# OLED_Shield.net
KiCad netlist of a schematic drawn in EAGLE
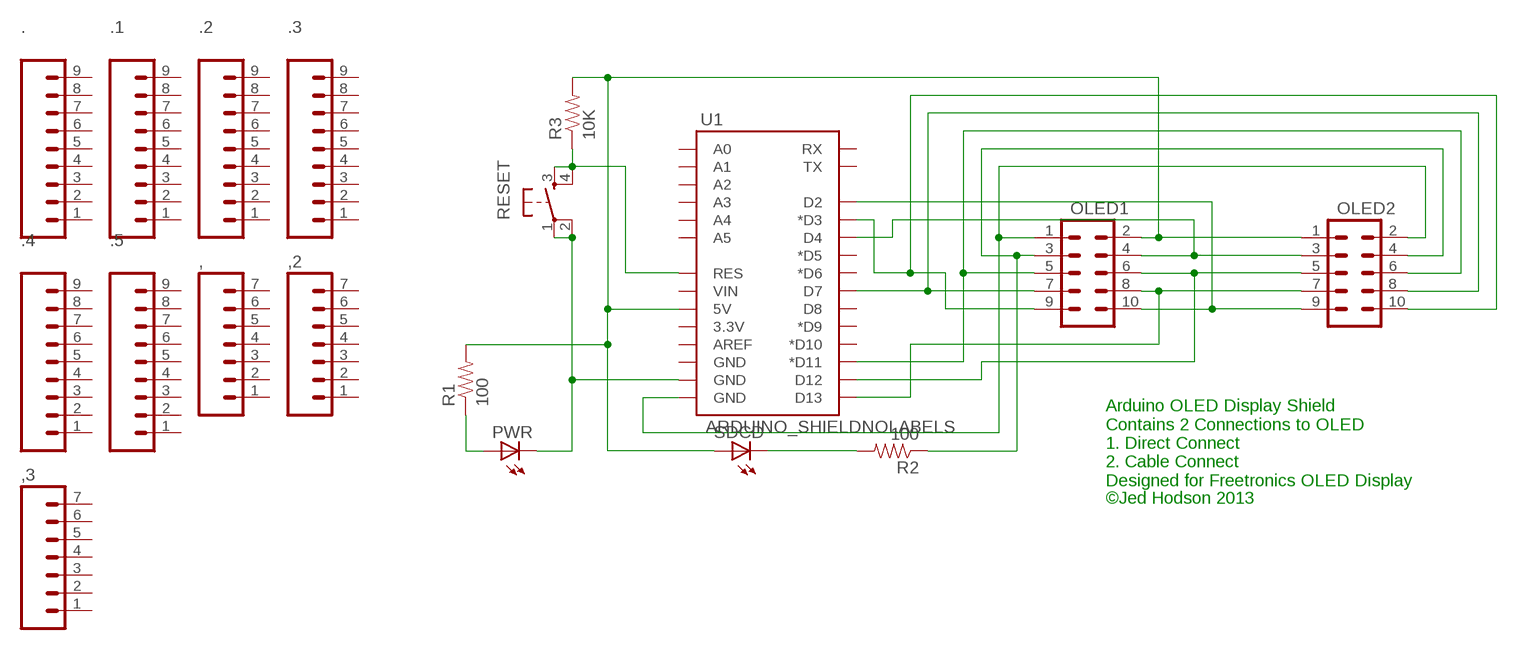
[diagram p0: schematic, sheet 1]

(export (version "E")
  (design (tool "Eeschema 10.0.6"))
  (components
    (comp (ref ",")
      (value "M07")
      (footprint "eagle-import:1X07")
      (libsource (lib "eagle-import") (part "M07"))
    )
    (comp (ref ",2")
      (value "M07")
      (footprint "eagle-import:1X07")
      (libsource (lib "eagle-import") (part "M07"))
    )
    (comp (ref ",3")
      (value "M07")
      (footprint "eagle-import:1X07")
      (libsource (lib "eagle-import") (part "M07"))
    )
    (comp (ref ".")
      (value "M09")
      (footprint "eagle-import:1X09")
      (libsource (lib "eagle-import") (part "M09"))
    )
    (comp (ref ".1")
      (value "M09")
      (footprint "eagle-import:1X09")
      (libsource (lib "eagle-import") (part "M09"))
    )
    (comp (ref ".2")
      (value "M09")
      (footprint "eagle-import:1X09")
      (libsource (lib "eagle-import") (part "M09"))
    )
    (comp (ref ".3")
      (value "M09")
      (footprint "eagle-import:1X09")
      (libsource (lib "eagle-import") (part "M09"))
    )
    (comp (ref ".4")
      (value "M09")
      (footprint "eagle-import:1X09")
      (libsource (lib "eagle-import") (part "M09"))
    )
    (comp (ref ".5")
      (value "M09")
      (footprint "eagle-import:1X09")
      (libsource (lib "eagle-import") (part "M09"))
    )
    (comp (ref "OLED1")
      (value "M05X2PTH")
      (footprint "eagle-import:AVR_ICSP")
      (libsource (lib "eagle-import") (part "M05X2PTH"))
    )
    (comp (ref "OLED2")
      (value "M05X2PTH")
      (footprint "eagle-import:AVR_ICSP")
      (libsource (lib "eagle-import") (part "M05X2PTH"))
    )
    (comp (ref "PWR")
      (value "LED5MM")
      (footprint "eagle-import:LED5MM")
      (libsource (lib "eagle-import") (part "LED5MM"))
    )
    (comp (ref "R1")
      (value "100")
      (footprint "eagle-import:AXIAL-0.4")
      (libsource (lib "eagle-import") (part "RESISTORPTH-1/4W"))
    )
    (comp (ref "R2")
      (value "100")
      (footprint "eagle-import:AXIAL-0.4")
      (libsource (lib "eagle-import") (part "RESISTORPTH-1/4W"))
    )
    (comp (ref "R3")
      (value "10K")
      (footprint "eagle-import:AXIAL-0.4")
      (libsource (lib "eagle-import") (part "RESISTORPTH-1/4W"))
    )
    (comp (ref "RESET")
      (value "TAC_SWITCHPTH")
      (footprint "eagle-import:TACTILE-PTH")
      (libsource (lib "eagle-import") (part "TAC_SWITCHPTH"))
    )
    (comp (ref "SDCD")
      (value "LED5MM")
      (footprint "eagle-import:LED5MM")
      (libsource (lib "eagle-import") (part "LED5MM"))
    )
    (comp (ref "U1")
      (value "ARDUINO_SHIELDNOLABELS")
      (footprint "eagle-import:DUEMILANOVE_SHIELD_NOLABELS")
      (libsource (lib "eagle-import") (part "ARDUINO_SHIELDNOLABELS"))
    )
  )
  (nets
    (net (code "1") (name "Net-(OLED1-Pad1)") (class "Default")
      (node (ref "OLED1") (pin "1") (pinfunction "1_1") (pintype "passive"))
      (node (ref "OLED2") (pin "2") (pinfunction "2_2") (pintype "passive"))
      (node (ref "U1") (pin "GND@0") (pinfunction "GND_GND@0") (pintype "bidirectional"))
    )
    (net (code "2") (name "Net-(OLED1-Pad4)") (class "Default")
      (node (ref "OLED1") (pin "4") (pinfunction "4_4") (pintype "passive"))
      (node (ref "OLED2") (pin "3") (pinfunction "3_3") (pintype "passive"))
      (node (ref "U1") (pin "D4") (pinfunction "D4_D4") (pintype "bidirectional"))
    )
    (net (code "3") (name "Net-(OLED1-Pad6)") (class "Default")
      (node (ref "OLED1") (pin "6") (pinfunction "6_6") (pintype "passive"))
      (node (ref "OLED2") (pin "5") (pinfunction "5_5") (pintype "passive"))
      (node (ref "U1") (pin "D12") (pinfunction "D12_D12") (pintype "bidirectional"))
    )
    (net (code "4") (name "Net-(OLED1-Pad7)") (class "Default")
      (node (ref "OLED1") (pin "7") (pinfunction "7_7") (pintype "passive"))
      (node (ref "OLED2") (pin "8") (pinfunction "8_8") (pintype "passive"))
      (node (ref "U1") (pin "D7") (pinfunction "D7_D7") (pintype "bidirectional"))
    )
    (net (code "5") (name "Net-(OLED1-Pad8)") (class "Default")
      (node (ref "OLED1") (pin "8") (pinfunction "8_8") (pintype "passive"))
      (node (ref "OLED2") (pin "7") (pinfunction "7_7") (pintype "passive"))
      (node (ref "U1") (pin "D13") (pinfunction "D13_D13") (pintype "bidirectional"))
    )
    (net (code "6") (name "Net-(OLED1-Pad10)") (class "Default")
      (node (ref "OLED1") (pin "10") (pinfunction "10_10") (pintype "passive"))
      (node (ref "OLED2") (pin "9") (pinfunction "9_9") (pintype "passive"))
      (node (ref "U1") (pin "D2") (pinfunction "D2_D2") (pintype "bidirectional"))
    )
    (net (code "7") (name "Net-(PWR-C)") (class "Default")
      (node (ref "PWR") (pin "K") (pinfunction "C_K") (pintype "passive"))
      (node (ref "RESET") (pin "1") (pinfunction "1_1") (pintype "passive"))
      (node (ref "RESET") (pin "2") (pinfunction "2_2") (pintype "passive"))
      (node (ref "U1") (pin "GND@1") (pinfunction "GND_GND@1") (pintype "bidirectional"))
    )
    (net (code "8") (name "Net-(R1-1)") (class "Default")
      (node (ref "PWR") (pin "A") (pinfunction "A_A") (pintype "passive"))
      (node (ref "R1") (pin "P$1") (pinfunction "1_P$1") (pintype "passive"))
    )
    (net (code "9") (name "Net-(R1-2)") (class "Default")
      (node (ref "OLED1") (pin "2") (pinfunction "2_2") (pintype "passive"))
      (node (ref "OLED2") (pin "1") (pinfunction "1_1") (pintype "passive"))
      (node (ref "R1") (pin "P$2") (pinfunction "2_P$2") (pintype "passive"))
      (node (ref "R3") (pin "P$2") (pinfunction "2_P$2") (pintype "passive"))
      (node (ref "SDCD") (pin "A") (pinfunction "A_A") (pintype "passive"))
      (node (ref "U1") (pin "5V") (pinfunction "5V_5V") (pintype "bidirectional"))
    )
    (net (code "10") (name "Net-(R2-1)") (class "Default")
      (node (ref "OLED1") (pin "3") (pinfunction "3_3") (pintype "passive"))
      (node (ref "OLED2") (pin "4") (pinfunction "4_4") (pintype "passive"))
      (node (ref "R2") (pin "P$1") (pinfunction "1_P$1") (pintype "passive"))
    )
    (net (code "11") (name "Net-(R2-2)") (class "Default")
      (node (ref "R2") (pin "P$2") (pinfunction "2_P$2") (pintype "passive"))
      (node (ref "SDCD") (pin "K") (pinfunction "C_K") (pintype "passive"))
    )
    (net (code "12") (name "Net-(R3-1)") (class "Default")
      (node (ref "R3") (pin "P$1") (pinfunction "1_P$1") (pintype "passive"))
      (node (ref "RESET") (pin "3") (pinfunction "3_3") (pintype "passive"))
      (node (ref "RESET") (pin "4") (pinfunction "4_4") (pintype "passive"))
      (node (ref "U1") (pin "RES") (pinfunction "RES_RES") (pintype "bidirectional"))
    )
    (net (code "13") (name "Net-(U1-*D3)") (class "Default")
      (node (ref "OLED1") (pin "9") (pinfunction "9_9") (pintype "passive"))
      (node (ref "OLED2") (pin "10") (pinfunction "10_10") (pintype "passive"))
      (node (ref "U1") (pin "D3") (pinfunction "*D3_D3") (pintype "bidirectional"))
    )
    (net (code "14") (name "Net-(U1-*D11)") (class "Default")
      (node (ref "OLED1") (pin "5") (pinfunction "5_5") (pintype "passive"))
      (node (ref "OLED2") (pin "6") (pinfunction "6_6") (pintype "passive"))
      (node (ref "U1") (pin "D11") (pinfunction "*D11_D11") (pintype "bidirectional"))
    )
    (net (code "15") (name "unconnected-(,-Pad1)") (class "Default")
      (node (ref ",") (pin "1") (pinfunction "1_1") (pintype "passive"))
    )
    (net (code "16") (name "unconnected-(,-Pad2)") (class "Default")
      (node (ref ",") (pin "2") (pinfunction "2_2") (pintype "passive"))
    )
    (net (code "17") (name "unconnected-(,-Pad3)") (class "Default")
      (node (ref ",") (pin "3") (pinfunction "3_3") (pintype "passive"))
    )
    (net (code "18") (name "unconnected-(,-Pad4)") (class "Default")
      (node (ref ",") (pin "4") (pinfunction "4_4") (pintype "passive"))
    )
    (net (code "19") (name "unconnected-(,-Pad5)") (class "Default")
      (node (ref ",") (pin "5") (pinfunction "5_5") (pintype "passive"))
    )
    (net (code "20") (name "unconnected-(,-Pad6)") (class "Default")
      (node (ref ",") (pin "6") (pinfunction "6_6") (pintype "passive"))
    )
    (net (code "21") (name "unconnected-(,-Pad7)") (class "Default")
      (node (ref ",") (pin "7") (pinfunction "7_7") (pintype "passive"))
    )
    (net (code "22") (name "unconnected-(,2-Pad1)") (class "Default")
      (node (ref ",2") (pin "1") (pinfunction "1_1") (pintype "passive"))
    )
    (net (code "23") (name "unconnected-(,2-Pad2)") (class "Default")
      (node (ref ",2") (pin "2") (pinfunction "2_2") (pintype "passive"))
    )
    (net (code "24") (name "unconnected-(,2-Pad3)") (class "Default")
      (node (ref ",2") (pin "3") (pinfunction "3_3") (pintype "passive"))
    )
    (net (code "25") (name "unconnected-(,2-Pad4)") (class "Default")
      (node (ref ",2") (pin "4") (pinfunction "4_4") (pintype "passive"))
    )
    (net (code "26") (name "unconnected-(,2-Pad5)") (class "Default")
      (node (ref ",2") (pin "5") (pinfunction "5_5") (pintype "passive"))
    )
    (net (code "27") (name "unconnected-(,2-Pad6)") (class "Default")
      (node (ref ",2") (pin "6") (pinfunction "6_6") (pintype "passive"))
    )
    (net (code "28") (name "unconnected-(,2-Pad7)") (class "Default")
      (node (ref ",2") (pin "7") (pinfunction "7_7") (pintype "passive"))
    )
    (net (code "29") (name "unconnected-(,3-Pad1)") (class "Default")
      (node (ref ",3") (pin "1") (pinfunction "1_1") (pintype "passive"))
    )
    (net (code "30") (name "unconnected-(,3-Pad2)") (class "Default")
      (node (ref ",3") (pin "2") (pinfunction "2_2") (pintype "passive"))
    )
    (net (code "31") (name "unconnected-(,3-Pad3)") (class "Default")
      (node (ref ",3") (pin "3") (pinfunction "3_3") (pintype "passive"))
    )
    (net (code "32") (name "unconnected-(,3-Pad4)") (class "Default")
      (node (ref ",3") (pin "4") (pinfunction "4_4") (pintype "passive"))
    )
    (net (code "33") (name "unconnected-(,3-Pad5)") (class "Default")
      (node (ref ",3") (pin "5") (pinfunction "5_5") (pintype "passive"))
    )
    (net (code "34") (name "unconnected-(,3-Pad6)") (class "Default")
      (node (ref ",3") (pin "6") (pinfunction "6_6") (pintype "passive"))
    )
    (net (code "35") (name "unconnected-(,3-Pad7)") (class "Default")
      (node (ref ",3") (pin "7") (pinfunction "7_7") (pintype "passive"))
    )
    (net (code "36") (name "unconnected-(.-Pad1)") (class "Default")
      (node (ref ".") (pin "1") (pinfunction "1_1") (pintype "passive"))
    )
    (net (code "37") (name "unconnected-(.-Pad2)") (class "Default")
      (node (ref ".") (pin "2") (pinfunction "2_2") (pintype "passive"))
    )
    (net (code "38") (name "unconnected-(.-Pad3)") (class "Default")
      (node (ref ".") (pin "3") (pinfunction "3_3") (pintype "passive"))
    )
    (net (code "39") (name "unconnected-(.-Pad4)") (class "Default")
      (node (ref ".") (pin "4") (pinfunction "4_4") (pintype "passive"))
    )
    (net (code "40") (name "unconnected-(.-Pad5)") (class "Default")
      (node (ref ".") (pin "5") (pinfunction "5_5") (pintype "passive"))
    )
    (net (code "41") (name "unconnected-(.-Pad6)") (class "Default")
      (node (ref ".") (pin "6") (pinfunction "6_6") (pintype "passive"))
    )
    (net (code "42") (name "unconnected-(.-Pad7)") (class "Default")
      (node (ref ".") (pin "7") (pinfunction "7_7") (pintype "passive"))
    )
    (net (code "43") (name "unconnected-(.-Pad8)") (class "Default")
      (node (ref ".") (pin "8") (pinfunction "8_8") (pintype "passive"))
    )
    (net (code "44") (name "unconnected-(.-Pad9)") (class "Default")
      (node (ref ".") (pin "9") (pinfunction "9_9") (pintype "passive"))
    )
    (net (code "45") (name "unconnected-(.1-Pad1)") (class "Default")
      (node (ref ".1") (pin "1") (pinfunction "1_1") (pintype "passive"))
    )
    (net (code "46") (name "unconnected-(.1-Pad2)") (class "Default")
      (node (ref ".1") (pin "2") (pinfunction "2_2") (pintype "passive"))
    )
    (net (code "47") (name "unconnected-(.1-Pad3)") (class "Default")
      (node (ref ".1") (pin "3") (pinfunction "3_3") (pintype "passive"))
    )
    (net (code "48") (name "unconnected-(.1-Pad4)") (class "Default")
      (node (ref ".1") (pin "4") (pinfunction "4_4") (pintype "passive"))
    )
    (net (code "49") (name "unconnected-(.1-Pad5)") (class "Default")
      (node (ref ".1") (pin "5") (pinfunction "5_5") (pintype "passive"))
    )
    (net (code "50") (name "unconnected-(.1-Pad6)") (class "Default")
      (node (ref ".1") (pin "6") (pinfunction "6_6") (pintype "passive"))
    )
    (net (code "51") (name "unconnected-(.1-Pad7)") (class "Default")
      (node (ref ".1") (pin "7") (pinfunction "7_7") (pintype "passive"))
    )
    (net (code "52") (name "unconnected-(.1-Pad8)") (class "Default")
      (node (ref ".1") (pin "8") (pinfunction "8_8") (pintype "passive"))
    )
    (net (code "53") (name "unconnected-(.1-Pad9)") (class "Default")
      (node (ref ".1") (pin "9") (pinfunction "9_9") (pintype "passive"))
    )
    (net (code "54") (name "unconnected-(.2-Pad1)") (class "Default")
      (node (ref ".2") (pin "1") (pinfunction "1_1") (pintype "passive"))
    )
    (net (code "55") (name "unconnected-(.2-Pad2)") (class "Default")
      (node (ref ".2") (pin "2") (pinfunction "2_2") (pintype "passive"))
    )
    (net (code "56") (name "unconnected-(.2-Pad3)") (class "Default")
      (node (ref ".2") (pin "3") (pinfunction "3_3") (pintype "passive"))
    )
    (net (code "57") (name "unconnected-(.2-Pad4)") (class "Default")
      (node (ref ".2") (pin "4") (pinfunction "4_4") (pintype "passive"))
    )
    (net (code "58") (name "unconnected-(.2-Pad5)") (class "Default")
      (node (ref ".2") (pin "5") (pinfunction "5_5") (pintype "passive"))
    )
    (net (code "59") (name "unconnected-(.2-Pad6)") (class "Default")
      (node (ref ".2") (pin "6") (pinfunction "6_6") (pintype "passive"))
    )
    (net (code "60") (name "unconnected-(.2-Pad7)") (class "Default")
      (node (ref ".2") (pin "7") (pinfunction "7_7") (pintype "passive"))
    )
    (net (code "61") (name "unconnected-(.2-Pad8)") (class "Default")
      (node (ref ".2") (pin "8") (pinfunction "8_8") (pintype "passive"))
    )
    (net (code "62") (name "unconnected-(.2-Pad9)") (class "Default")
      (node (ref ".2") (pin "9") (pinfunction "9_9") (pintype "passive"))
    )
    (net (code "63") (name "unconnected-(.3-Pad1)") (class "Default")
      (node (ref ".3") (pin "1") (pinfunction "1_1") (pintype "passive"))
    )
    (net (code "64") (name "unconnected-(.3-Pad2)") (class "Default")
      (node (ref ".3") (pin "2") (pinfunction "2_2") (pintype "passive"))
    )
    (net (code "65") (name "unconnected-(.3-Pad3)") (class "Default")
      (node (ref ".3") (pin "3") (pinfunction "3_3") (pintype "passive"))
    )
    (net (code "66") (name "unconnected-(.3-Pad4)") (class "Default")
      (node (ref ".3") (pin "4") (pinfunction "4_4") (pintype "passive"))
    )
    (net (code "67") (name "unconnected-(.3-Pad5)") (class "Default")
      (node (ref ".3") (pin "5") (pinfunction "5_5") (pintype "passive"))
    )
    (net (code "68") (name "unconnected-(.3-Pad6)") (class "Default")
      (node (ref ".3") (pin "6") (pinfunction "6_6") (pintype "passive"))
    )
    (net (code "69") (name "unconnected-(.3-Pad7)") (class "Default")
      (node (ref ".3") (pin "7") (pinfunction "7_7") (pintype "passive"))
    )
    (net (code "70") (name "unconnected-(.3-Pad8)") (class "Default")
      (node (ref ".3") (pin "8") (pinfunction "8_8") (pintype "passive"))
    )
    (net (code "71") (name "unconnected-(.3-Pad9)") (class "Default")
      (node (ref ".3") (pin "9") (pinfunction "9_9") (pintype "passive"))
    )
    (net (code "72") (name "unconnected-(.4-Pad1)") (class "Default")
      (node (ref ".4") (pin "1") (pinfunction "1_1") (pintype "passive"))
    )
    (net (code "73") (name "unconnected-(.4-Pad2)") (class "Default")
      (node (ref ".4") (pin "2") (pinfunction "2_2") (pintype "passive"))
    )
    (net (code "74") (name "unconnected-(.4-Pad3)") (class "Default")
      (node (ref ".4") (pin "3") (pinfunction "3_3") (pintype "passive"))
    )
    (net (code "75") (name "unconnected-(.4-Pad4)") (class "Default")
      (node (ref ".4") (pin "4") (pinfunction "4_4") (pintype "passive"))
    )
    (net (code "76") (name "unconnected-(.4-Pad5)") (class "Default")
      (node (ref ".4") (pin "5") (pinfunction "5_5") (pintype "passive"))
    )
    (net (code "77") (name "unconnected-(.4-Pad6)") (class "Default")
      (node (ref ".4") (pin "6") (pinfunction "6_6") (pintype "passive"))
    )
    (net (code "78") (name "unconnected-(.4-Pad7)") (class "Default")
      (node (ref ".4") (pin "7") (pinfunction "7_7") (pintype "passive"))
    )
    (net (code "79") (name "unconnected-(.4-Pad8)") (class "Default")
      (node (ref ".4") (pin "8") (pinfunction "8_8") (pintype "passive"))
    )
    (net (code "80") (name "unconnected-(.4-Pad9)") (class "Default")
      (node (ref ".4") (pin "9") (pinfunction "9_9") (pintype "passive"))
    )
    (net (code "81") (name "unconnected-(.5-Pad1)") (class "Default")
      (node (ref ".5") (pin "1") (pinfunction "1_1") (pintype "passive"))
    )
    (net (code "82") (name "unconnected-(.5-Pad2)") (class "Default")
      (node (ref ".5") (pin "2") (pinfunction "2_2") (pintype "passive"))
    )
    (net (code "83") (name "unconnected-(.5-Pad3)") (class "Default")
      (node (ref ".5") (pin "3") (pinfunction "3_3") (pintype "passive"))
    )
    (net (code "84") (name "unconnected-(.5-Pad4)") (class "Default")
      (node (ref ".5") (pin "4") (pinfunction "4_4") (pintype "passive"))
    )
    (net (code "85") (name "unconnected-(.5-Pad5)") (class "Default")
      (node (ref ".5") (pin "5") (pinfunction "5_5") (pintype "passive"))
    )
    (net (code "86") (name "unconnected-(.5-Pad6)") (class "Default")
      (node (ref ".5") (pin "6") (pinfunction "6_6") (pintype "passive"))
    )
    (net (code "87") (name "unconnected-(.5-Pad7)") (class "Default")
      (node (ref ".5") (pin "7") (pinfunction "7_7") (pintype "passive"))
    )
    (net (code "88") (name "unconnected-(.5-Pad8)") (class "Default")
      (node (ref ".5") (pin "8") (pinfunction "8_8") (pintype "passive"))
    )
    (net (code "89") (name "unconnected-(.5-Pad9)") (class "Default")
      (node (ref ".5") (pin "9") (pinfunction "9_9") (pintype "passive"))
    )
    (net (code "90") (name "unconnected-(U1-*D5-PadD5)") (class "Default")
      (node (ref "U1") (pin "D5") (pinfunction "*D5_D5") (pintype "bidirectional"))
    )
    (net (code "91") (name "unconnected-(U1-*D6-PadD6)") (class "Default")
      (node (ref "U1") (pin "D6") (pinfunction "*D6_D6") (pintype "bidirectional"))
    )
    (net (code "92") (name "unconnected-(U1-*D9-PadD9)") (class "Default")
      (node (ref "U1") (pin "D9") (pinfunction "*D9_D9") (pintype "bidirectional"))
    )
    (net (code "93") (name "unconnected-(U1-*D10-PadD10)") (class "Default")
      (node (ref "U1") (pin "D10") (pinfunction "*D10_D10") (pintype "bidirectional"))
    )
    (net (code "94") (name "unconnected-(U1-GND-PadGND@2)") (class "Default")
      (node (ref "U1") (pin "GND@2") (pinfunction "GND_GND@2") (pintype "bidirectional"))
    )
    (net (code "95") (name "unconnected-(U1-Pad3.3V)") (class "Default")
      (node (ref "U1") (pin "3.3V") (pinfunction "3.3V_3.3V") (pintype "bidirectional"))
    )
    (net (code "96") (name "unconnected-(U1-PadA0)") (class "Default")
      (node (ref "U1") (pin "A0") (pinfunction "A0_A0") (pintype "bidirectional"))
    )
    (net (code "97") (name "unconnected-(U1-PadA1)") (class "Default")
      (node (ref "U1") (pin "A1") (pinfunction "A1_A1") (pintype "bidirectional"))
    )
    (net (code "98") (name "unconnected-(U1-PadA2)") (class "Default")
      (node (ref "U1") (pin "A2") (pinfunction "A2_A2") (pintype "bidirectional"))
    )
    (net (code "99") (name "unconnected-(U1-PadA3)") (class "Default")
      (node (ref "U1") (pin "A3") (pinfunction "A3_A3") (pintype "bidirectional"))
    )
    (net (code "100") (name "unconnected-(U1-PadA4)") (class "Default")
      (node (ref "U1") (pin "A4") (pinfunction "A4_A4") (pintype "bidirectional"))
    )
    (net (code "101") (name "unconnected-(U1-PadA5)") (class "Default")
      (node (ref "U1") (pin "A5") (pinfunction "A5_A5") (pintype "bidirectional"))
    )
    (net (code "102") (name "unconnected-(U1-PadAREF)") (class "Default")
      (node (ref "U1") (pin "AREF") (pinfunction "AREF_AREF") (pintype "bidirectional"))
    )
    (net (code "103") (name "unconnected-(U1-PadD8)") (class "Default")
      (node (ref "U1") (pin "D8") (pinfunction "D8_D8") (pintype "bidirectional"))
    )
    (net (code "104") (name "unconnected-(U1-PadRX)") (class "Default")
      (node (ref "U1") (pin "RX") (pinfunction "RX_RX") (pintype "bidirectional"))
    )
    (net (code "105") (name "unconnected-(U1-PadTX)") (class "Default")
      (node (ref "U1") (pin "TX") (pinfunction "TX_TX") (pintype "bidirectional"))
    )
    (net (code "106") (name "unconnected-(U1-PadVIN)") (class "Default")
      (node (ref "U1") (pin "VIN") (pinfunction "VIN_VIN") (pintype "bidirectional"))
    )
  )
)
